# Mezzanine_9DOF.net
KiCad netlist of a schematic drawn in EAGLE
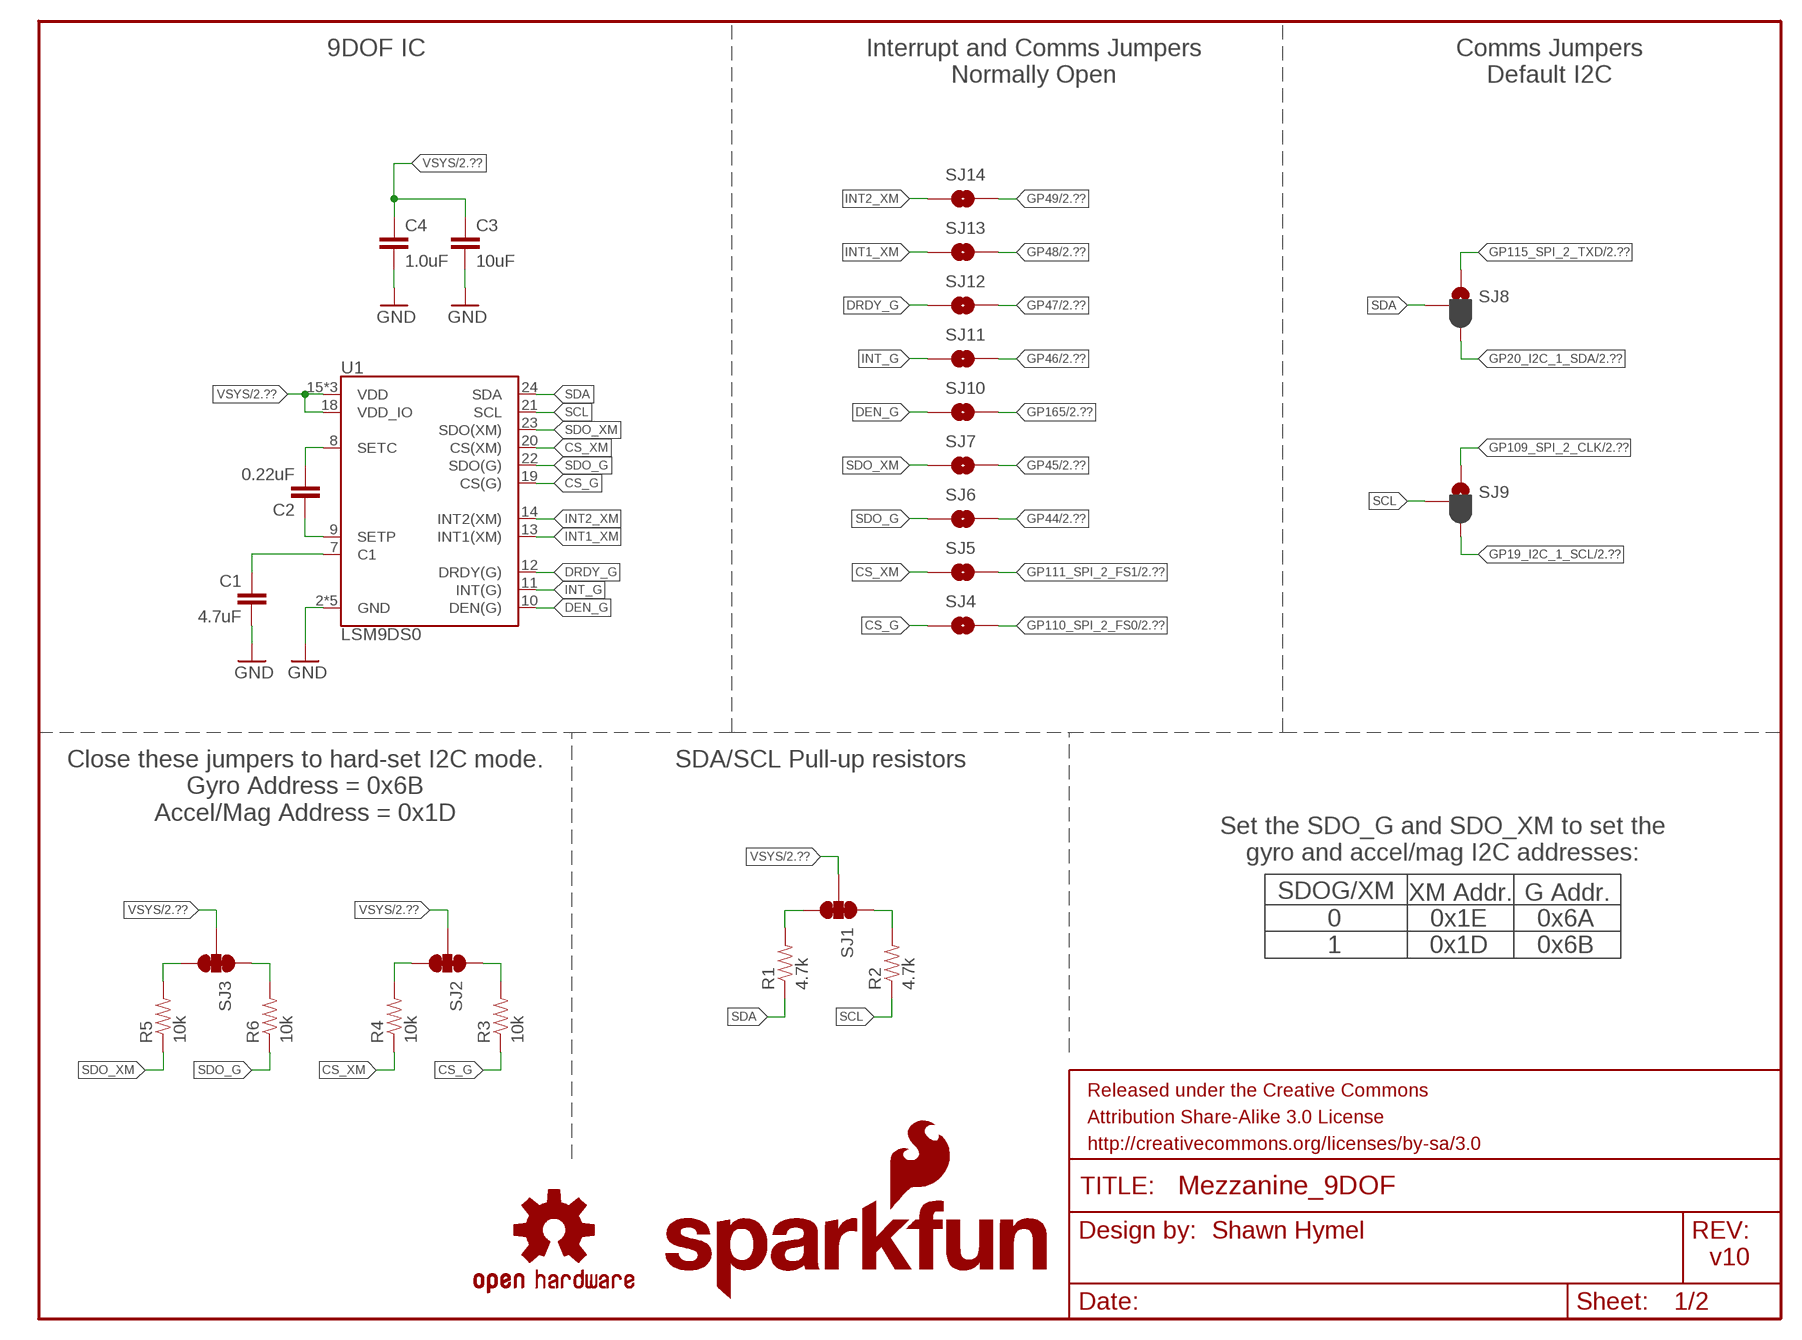
[diagram p0: schematic, sheet 1]
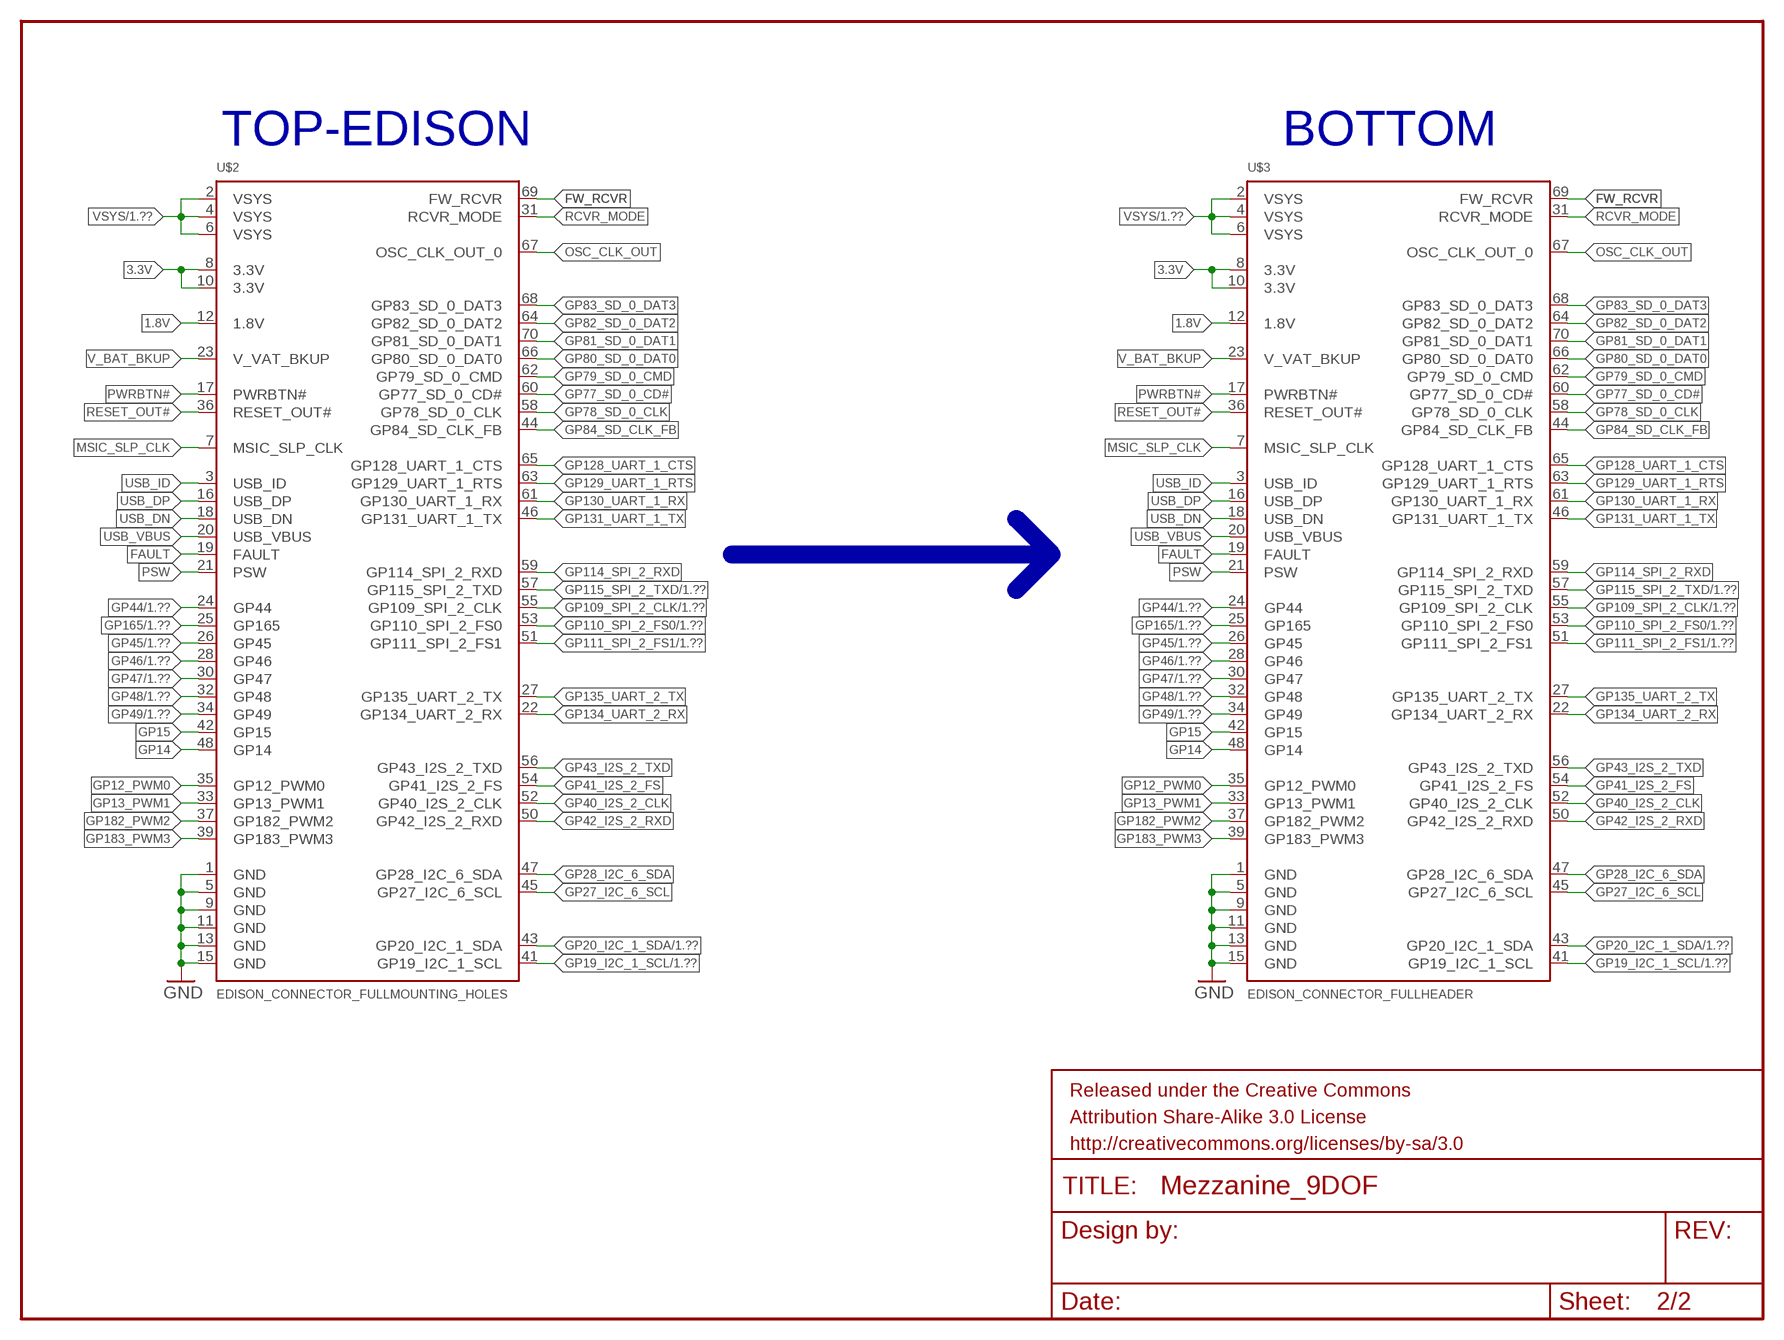
[diagram p1: schematic, sheet 2]

(export (version "E")
  (design (tool "Eeschema 10.0.6"))
  (components
    (comp (ref "FRAME2")
      (value "FRAME-LETTER")
      (footprint "eagle-import:CREATIVE_COMMONS")
      (libsource (lib "eagle-import") (part "FRAME-LETTER"))
    )
    (comp (ref "U$2")
      (value "EDISON_CONNECTOR_FULLMOUNTING_HOLES")
      (footprint "eagle-import:EDISON_DAUGHTER")
      (libsource (lib "eagle-import") (part "EDISON_CONNECTOR_FULLMOUNTING_HOLES"))
    )
    (comp (ref "U$3")
      (value "EDISON_CONNECTOR_FULLHEADER")
      (footprint "eagle-import:DF40C-70DP-0.4(51)")
      (libsource (lib "eagle-import") (part "EDISON_CONNECTOR_FULLHEADER"))
    )
    (comp (ref "C1")
      (value "4.7uF")
      (footprint "eagle-import:0603-CAP")
      (libsource (lib "eagle-import") (part "4.7UF-6.3V-10%(0603)0603"))
    )
    (comp (ref "C2")
      (value "0.22uF")
      (footprint "eagle-import:0603-CAP")
      (libsource (lib "eagle-import") (part "0.22UF-25V-10%(0603)"))
    )
    (comp (ref "C3")
      (value "10uF")
      (footprint "eagle-import:0805")
      (libsource (lib "eagle-import") (part "CAP0805"))
    )
    (comp (ref "C4")
      (value "1.0uF")
      (footprint "eagle-import:0603-CAP")
      (libsource (lib "eagle-import") (part "1.0UF-16V-10%(0603)"))
    )
    (comp (ref "FRAME1")
      (value "FRAME-LETTER")
      (footprint "eagle-import:CREATIVE_COMMONS")
      (libsource (lib "eagle-import") (part "FRAME-LETTER"))
    )
    (comp (ref "LOGO2")
      (value "OSHW-LOGOS")
      (footprint "eagle-import:OSHW-LOGO-S")
      (libsource (lib "eagle-import") (part "OSHW-LOGOS"))
    )
    (comp (ref "LOGO3")
      (value "SFE_LOGO_NAME_FLAME.1_INCH")
      (footprint "eagle-import:SFE_LOGO_NAME_FLAME_.1")
      (libsource (lib "eagle-import") (part "SFE_LOGO_NAME_FLAME.1_INCH"))
    )
    (comp (ref "R1")
      (value "4.7k")
      (footprint "eagle-import:0603-RES")
      (libsource (lib "eagle-import") (part "10K-1%RES-00824"))
    )
    (comp (ref "R2")
      (value "4.7k")
      (footprint "eagle-import:0603-RES")
      (libsource (lib "eagle-import") (part "10K-1%RES-00824"))
    )
    (comp (ref "R3")
      (value "10k")
      (footprint "eagle-import:0603-RES")
      (libsource (lib "eagle-import") (part "10K-1%RES-00824"))
    )
    (comp (ref "R4")
      (value "10k")
      (footprint "eagle-import:0603-RES")
      (libsource (lib "eagle-import") (part "10K-1%RES-00824"))
    )
    (comp (ref "R5")
      (value "10k")
      (footprint "eagle-import:0603-RES")
      (libsource (lib "eagle-import") (part "10K-1%RES-00824"))
    )
    (comp (ref "R6")
      (value "10k")
      (footprint "eagle-import:0603-RES")
      (libsource (lib "eagle-import") (part "10K-1%RES-00824"))
    )
    (comp (ref "SJ1")
      (value "SOLDERJUMPER_2WAYS")
      (footprint "eagle-import:SJ_3")
      (libsource (lib "eagle-import") (part "SOLDERJUMPER_2WAYS"))
    )
    (comp (ref "SJ2")
      (value "SOLDERJUMPER_2WAYS")
      (footprint "eagle-import:SJ_3")
      (libsource (lib "eagle-import") (part "SOLDERJUMPER_2WAYS"))
    )
    (comp (ref "SJ3")
      (value "SOLDERJUMPER_2WAYS")
      (footprint "eagle-import:SJ_3")
      (libsource (lib "eagle-import") (part "SOLDERJUMPER_2WAYS"))
    )
    (comp (ref "SJ4")
      (value "JUMPER-PAD-2-NOYES_SILK")
      (footprint "eagle-import:PAD-JUMPER-2-NO_YES_SILK")
      (libsource (lib "eagle-import") (part "JUMPER-PAD-2-NOYES_SILK"))
    )
    (comp (ref "SJ5")
      (value "JUMPER-PAD-2-NOYES_SILK")
      (footprint "eagle-import:PAD-JUMPER-2-NO_YES_SILK")
      (libsource (lib "eagle-import") (part "JUMPER-PAD-2-NOYES_SILK"))
    )
    (comp (ref "SJ6")
      (value "JUMPER-PAD-2-NOYES_SILK")
      (footprint "eagle-import:PAD-JUMPER-2-NO_YES_SILK")
      (libsource (lib "eagle-import") (part "JUMPER-PAD-2-NOYES_SILK"))
    )
    (comp (ref "SJ7")
      (value "JUMPER-PAD-2-NOYES_SILK")
      (footprint "eagle-import:PAD-JUMPER-2-NO_YES_SILK")
      (libsource (lib "eagle-import") (part "JUMPER-PAD-2-NOYES_SILK"))
    )
    (comp (ref "SJ8")
      (value "JUMPER-PAD-3-2OF3_NC_BY_PASTE")
      (footprint "eagle-import:PAD-JUMPER-3-2OF3_NC_BY_PASTE_YES_SILK_FULL_BOX")
      (libsource (lib "eagle-import") (part "JUMPER-PAD-3-2OF3_NC_BY_PASTE"))
    )
    (comp (ref "SJ9")
      (value "JUMPER-PAD-3-2OF3_NC_BY_PASTE")
      (footprint "eagle-import:PAD-JUMPER-3-2OF3_NC_BY_PASTE_YES_SILK_FULL_BOX")
      (libsource (lib "eagle-import") (part "JUMPER-PAD-3-2OF3_NC_BY_PASTE"))
    )
    (comp (ref "SJ10")
      (value "JUMPER-PAD-2-NOYES_SILK")
      (footprint "eagle-import:PAD-JUMPER-2-NO_YES_SILK")
      (libsource (lib "eagle-import") (part "JUMPER-PAD-2-NOYES_SILK"))
    )
    (comp (ref "SJ11")
      (value "JUMPER-PAD-2-NOYES_SILK")
      (footprint "eagle-import:PAD-JUMPER-2-NO_YES_SILK")
      (libsource (lib "eagle-import") (part "JUMPER-PAD-2-NOYES_SILK"))
    )
    (comp (ref "SJ12")
      (value "JUMPER-PAD-2-NOYES_SILK")
      (footprint "eagle-import:PAD-JUMPER-2-NO_YES_SILK")
      (libsource (lib "eagle-import") (part "JUMPER-PAD-2-NOYES_SILK"))
    )
    (comp (ref "SJ13")
      (value "JUMPER-PAD-2-NOYES_SILK")
      (footprint "eagle-import:PAD-JUMPER-2-NO_YES_SILK")
      (libsource (lib "eagle-import") (part "JUMPER-PAD-2-NOYES_SILK"))
    )
    (comp (ref "SJ14")
      (value "JUMPER-PAD-2-NOYES_SILK")
      (footprint "eagle-import:PAD-JUMPER-2-NO_YES_SILK")
      (libsource (lib "eagle-import") (part "JUMPER-PAD-2-NOYES_SILK"))
    )
    (comp (ref "U1")
      (value "LSM9DS0")
      (footprint "eagle-import:LGA-24")
      (libsource (lib "eagle-import") (part "LSM9DS0"))
    )
  )
  (nets
    (net (code "1") (name "1.8V") (class "Default")
      (node (ref "U$2") (pin "12") (pinfunction "1.8V_12") (pintype "bidirectional"))
      (node (ref "U$3") (pin "12") (pinfunction "1.8V_12") (pintype "bidirectional"))
    )
    (net (code "2") (name "3.3V") (class "Default")
      (node (ref "U$2") (pin "10") (pinfunction "3.3V_10") (pintype "bidirectional"))
      (node (ref "U$2") (pin "8") (pinfunction "3.3V_8") (pintype "bidirectional"))
      (node (ref "U$3") (pin "10") (pinfunction "3.3V_10") (pintype "bidirectional"))
      (node (ref "U$3") (pin "8") (pinfunction "3.3V_8") (pintype "bidirectional"))
    )
    (net (code "3") (name "CS_G") (class "Default")
      (node (ref "R3") (pin "1") (pinfunction "1_1") (pintype "passive"))
      (node (ref "SJ4") (pin "1") (pinfunction "1_1") (pintype "passive"))
      (node (ref "U1") (pin "19") (pinfunction "CS(G)_19") (pintype "bidirectional"))
    )
    (net (code "4") (name "CS_XM") (class "Default")
      (node (ref "R4") (pin "1") (pinfunction "1_1") (pintype "passive"))
      (node (ref "SJ5") (pin "1") (pinfunction "1_1") (pintype "passive"))
      (node (ref "U1") (pin "20") (pinfunction "CS(XM)_20") (pintype "bidirectional"))
    )
    (net (code "5") (name "DEN_G") (class "Default")
      (node (ref "SJ10") (pin "1") (pinfunction "1_1") (pintype "passive"))
      (node (ref "U1") (pin "10") (pinfunction "DEN(G)_10") (pintype "bidirectional"))
    )
    (net (code "6") (name "DRDY_G") (class "Default")
      (node (ref "SJ12") (pin "1") (pinfunction "1_1") (pintype "passive"))
      (node (ref "U1") (pin "12") (pinfunction "DRDY(G)_12") (pintype "bidirectional"))
    )
    (net (code "7") (name "FAULT") (class "Default")
      (node (ref "U$2") (pin "19") (pinfunction "FAULT_19") (pintype "bidirectional"))
      (node (ref "U$3") (pin "19") (pinfunction "FAULT_19") (pintype "bidirectional"))
    )
    (net (code "8") (name "FW_RCVR") (class "Default")
      (node (ref "U$2") (pin "69") (pinfunction "FW_RCVR_69") (pintype "bidirectional"))
      (node (ref "U$3") (pin "69") (pinfunction "FW_RCVR_69") (pintype "bidirectional"))
    )
    (net (code "9") (name "GND") (class "Default")
      (node (ref "C1") (pin "2") (pinfunction "2_2") (pintype "passive"))
      (node (ref "C3") (pin "2") (pinfunction "2_2") (pintype "passive"))
      (node (ref "C4") (pin "2") (pinfunction "2_2") (pintype "passive"))
      (node (ref "U$2") (pin "1") (pinfunction "GND_1") (pintype "bidirectional"))
      (node (ref "U$2") (pin "11") (pinfunction "GND_11") (pintype "bidirectional"))
      (node (ref "U$2") (pin "13") (pinfunction "GND_13") (pintype "bidirectional"))
      (node (ref "U$2") (pin "15") (pinfunction "GND_15") (pintype "bidirectional"))
      (node (ref "U$2") (pin "5") (pinfunction "GND_5") (pintype "bidirectional"))
      (node (ref "U$2") (pin "9") (pinfunction "GND_9") (pintype "bidirectional"))
      (node (ref "U$3") (pin "1") (pinfunction "GND_1") (pintype "bidirectional"))
      (node (ref "U$3") (pin "11") (pinfunction "GND_11") (pintype "bidirectional"))
      (node (ref "U$3") (pin "13") (pinfunction "GND_13") (pintype "bidirectional"))
      (node (ref "U$3") (pin "15") (pinfunction "GND_15") (pintype "bidirectional"))
      (node (ref "U$3") (pin "5") (pinfunction "GND_5") (pintype "bidirectional"))
      (node (ref "U$3") (pin "9") (pinfunction "GND_9") (pintype "bidirectional"))
      (node (ref "U1") (pin "2") (pinfunction "GND_2") (pintype "bidirectional"))
      (node (ref "U1") (pin "3") (pinfunction "GND_3") (pintype "bidirectional"))
      (node (ref "U1") (pin "4") (pinfunction "GND_4") (pintype "bidirectional"))
      (node (ref "U1") (pin "5") (pinfunction "GND_5") (pintype "bidirectional"))
      (node (ref "U1") (pin "6") (pinfunction "GND_6") (pintype "bidirectional"))
    )
    (net (code "10") (name "GP12_PWM0") (class "Default")
      (node (ref "U$2") (pin "35") (pinfunction "GP12_PWM0_35") (pintype "bidirectional"))
      (node (ref "U$3") (pin "35") (pinfunction "GP12_PWM0_35") (pintype "bidirectional"))
    )
    (net (code "11") (name "GP13_PWM1") (class "Default")
      (node (ref "U$2") (pin "33") (pinfunction "GP13_PWM1_33") (pintype "bidirectional"))
      (node (ref "U$3") (pin "33") (pinfunction "GP13_PWM1_33") (pintype "bidirectional"))
    )
    (net (code "12") (name "GP14") (class "Default")
      (node (ref "U$2") (pin "48") (pinfunction "GP14_48") (pintype "bidirectional"))
      (node (ref "U$3") (pin "48") (pinfunction "GP14_48") (pintype "bidirectional"))
    )
    (net (code "13") (name "GP15") (class "Default")
      (node (ref "U$2") (pin "42") (pinfunction "GP15_42") (pintype "bidirectional"))
      (node (ref "U$3") (pin "42") (pinfunction "GP15_42") (pintype "bidirectional"))
    )
    (net (code "14") (name "GP19_I2C_1_SCL") (class "Default")
      (node (ref "SJ9") (pin "3") (pinfunction "3_3") (pintype "passive"))
      (node (ref "U$2") (pin "41") (pinfunction "GP19_I2C_1_SCL_41") (pintype "bidirectional"))
      (node (ref "U$3") (pin "41") (pinfunction "GP19_I2C_1_SCL_41") (pintype "bidirectional"))
    )
    (net (code "15") (name "GP20_I2C_1_SDA") (class "Default")
      (node (ref "SJ8") (pin "3") (pinfunction "3_3") (pintype "passive"))
      (node (ref "U$2") (pin "43") (pinfunction "GP20_I2C_1_SDA_43") (pintype "bidirectional"))
      (node (ref "U$3") (pin "43") (pinfunction "GP20_I2C_1_SDA_43") (pintype "bidirectional"))
    )
    (net (code "16") (name "GP27_I2C_6_SCL") (class "Default")
      (node (ref "U$2") (pin "45") (pinfunction "GP27_I2C_6_SCL_45") (pintype "bidirectional"))
      (node (ref "U$3") (pin "45") (pinfunction "GP27_I2C_6_SCL_45") (pintype "bidirectional"))
    )
    (net (code "17") (name "GP28_I2C_6_SDA") (class "Default")
      (node (ref "U$2") (pin "47") (pinfunction "GP28_I2C_6_SDA_47") (pintype "bidirectional"))
      (node (ref "U$3") (pin "47") (pinfunction "GP28_I2C_6_SDA_47") (pintype "bidirectional"))
    )
    (net (code "18") (name "GP40_I2S_2_CLK") (class "Default")
      (node (ref "U$2") (pin "52") (pinfunction "GP40_I2S_2_CLK_52") (pintype "bidirectional"))
      (node (ref "U$3") (pin "52") (pinfunction "GP40_I2S_2_CLK_52") (pintype "bidirectional"))
    )
    (net (code "19") (name "GP41_I2S_2_FS") (class "Default")
      (node (ref "U$2") (pin "54") (pinfunction "GP41_I2S_2_FS_54") (pintype "bidirectional"))
      (node (ref "U$3") (pin "54") (pinfunction "GP41_I2S_2_FS_54") (pintype "bidirectional"))
    )
    (net (code "20") (name "GP42_I2S_2_RXD") (class "Default")
      (node (ref "U$2") (pin "50") (pinfunction "GP42_I2S_2_RXD_50") (pintype "bidirectional"))
      (node (ref "U$3") (pin "50") (pinfunction "GP42_I2S_2_RXD_50") (pintype "bidirectional"))
    )
    (net (code "21") (name "GP43_I2S_2_TXD") (class "Default")
      (node (ref "U$2") (pin "56") (pinfunction "GP43_I2S_2_TXD_56") (pintype "bidirectional"))
      (node (ref "U$3") (pin "56") (pinfunction "GP43_I2S_2_TXD_56") (pintype "bidirectional"))
    )
    (net (code "22") (name "GP44") (class "Default")
      (node (ref "SJ6") (pin "2") (pinfunction "2_2") (pintype "passive"))
      (node (ref "U$2") (pin "24") (pinfunction "GP44_24") (pintype "bidirectional"))
      (node (ref "U$3") (pin "24") (pinfunction "GP44_24") (pintype "bidirectional"))
    )
    (net (code "23") (name "GP45") (class "Default")
      (node (ref "SJ7") (pin "2") (pinfunction "2_2") (pintype "passive"))
      (node (ref "U$2") (pin "26") (pinfunction "GP45_26") (pintype "bidirectional"))
      (node (ref "U$3") (pin "26") (pinfunction "GP45_26") (pintype "bidirectional"))
    )
    (net (code "24") (name "GP46") (class "Default")
      (node (ref "SJ11") (pin "2") (pinfunction "2_2") (pintype "passive"))
      (node (ref "U$2") (pin "28") (pinfunction "GP46_28") (pintype "bidirectional"))
      (node (ref "U$3") (pin "28") (pinfunction "GP46_28") (pintype "bidirectional"))
    )
    (net (code "25") (name "GP47") (class "Default")
      (node (ref "SJ12") (pin "2") (pinfunction "2_2") (pintype "passive"))
      (node (ref "U$2") (pin "30") (pinfunction "GP47_30") (pintype "bidirectional"))
      (node (ref "U$3") (pin "30") (pinfunction "GP47_30") (pintype "bidirectional"))
    )
    (net (code "26") (name "GP48") (class "Default")
      (node (ref "SJ13") (pin "2") (pinfunction "2_2") (pintype "passive"))
      (node (ref "U$2") (pin "32") (pinfunction "GP48_32") (pintype "bidirectional"))
      (node (ref "U$3") (pin "32") (pinfunction "GP48_32") (pintype "bidirectional"))
    )
    (net (code "27") (name "GP49") (class "Default")
      (node (ref "SJ14") (pin "2") (pinfunction "2_2") (pintype "passive"))
      (node (ref "U$2") (pin "34") (pinfunction "GP49_34") (pintype "bidirectional"))
      (node (ref "U$3") (pin "34") (pinfunction "GP49_34") (pintype "bidirectional"))
    )
    (net (code "28") (name "GP77_SD_0_CD#") (class "Default")
      (node (ref "U$2") (pin "60") (pinfunction "GP77_SD_0_CD#_60") (pintype "bidirectional"))
      (node (ref "U$3") (pin "60") (pinfunction "GP77_SD_0_CD#_60") (pintype "bidirectional"))
    )
    (net (code "29") (name "GP78_SD_0_CLK") (class "Default")
      (node (ref "U$2") (pin "58") (pinfunction "GP78_SD_0_CLK_58") (pintype "bidirectional"))
      (node (ref "U$3") (pin "58") (pinfunction "GP78_SD_0_CLK_58") (pintype "bidirectional"))
    )
    (net (code "30") (name "GP79_SD_0_CMD") (class "Default")
      (node (ref "U$2") (pin "62") (pinfunction "GP79_SD_0_CMD_62") (pintype "bidirectional"))
      (node (ref "U$3") (pin "62") (pinfunction "GP79_SD_0_CMD_62") (pintype "bidirectional"))
    )
    (net (code "31") (name "GP80_SD_0_DAT0") (class "Default")
      (node (ref "U$2") (pin "66") (pinfunction "GP80_SD_0_DAT0_66") (pintype "bidirectional"))
      (node (ref "U$3") (pin "66") (pinfunction "GP80_SD_0_DAT0_66") (pintype "bidirectional"))
    )
    (net (code "32") (name "GP81_SD_0_DAT1") (class "Default")
      (node (ref "U$2") (pin "70") (pinfunction "GP81_SD_0_DAT1_70") (pintype "bidirectional"))
      (node (ref "U$3") (pin "70") (pinfunction "GP81_SD_0_DAT1_70") (pintype "bidirectional"))
    )
    (net (code "33") (name "GP82_SD_0_DAT2") (class "Default")
      (node (ref "U$2") (pin "64") (pinfunction "GP82_SD_0_DAT2_64") (pintype "bidirectional"))
      (node (ref "U$3") (pin "64") (pinfunction "GP82_SD_0_DAT2_64") (pintype "bidirectional"))
    )
    (net (code "34") (name "GP83_SD_0_DAT3") (class "Default")
      (node (ref "U$2") (pin "68") (pinfunction "GP83_SD_0_DAT3_68") (pintype "bidirectional"))
      (node (ref "U$3") (pin "68") (pinfunction "GP83_SD_0_DAT3_68") (pintype "bidirectional"))
    )
    (net (code "35") (name "GP84_SD_CLK_FB") (class "Default")
      (node (ref "U$2") (pin "44") (pinfunction "GP84_SD_CLK_FB_44") (pintype "bidirectional"))
      (node (ref "U$3") (pin "44") (pinfunction "GP84_SD_CLK_FB_44") (pintype "bidirectional"))
    )
    (net (code "36") (name "GP109_SPI_2_CLK") (class "Default")
      (node (ref "SJ9") (pin "1") (pinfunction "1_1") (pintype "passive"))
      (node (ref "U$2") (pin "55") (pinfunction "GP109_SPI_2_CLK_55") (pintype "bidirectional"))
      (node (ref "U$3") (pin "55") (pinfunction "GP109_SPI_2_CLK_55") (pintype "bidirectional"))
    )
    (net (code "37") (name "GP110_SPI_2_FS0") (class "Default")
      (node (ref "SJ4") (pin "2") (pinfunction "2_2") (pintype "passive"))
      (node (ref "U$2") (pin "53") (pinfunction "GP110_SPI_2_FS0_53") (pintype "bidirectional"))
      (node (ref "U$3") (pin "53") (pinfunction "GP110_SPI_2_FS0_53") (pintype "bidirectional"))
    )
    (net (code "38") (name "GP111_SPI_2_FS1") (class "Default")
      (node (ref "SJ5") (pin "2") (pinfunction "2_2") (pintype "passive"))
      (node (ref "U$2") (pin "51") (pinfunction "GP111_SPI_2_FS1_51") (pintype "bidirectional"))
      (node (ref "U$3") (pin "51") (pinfunction "GP111_SPI_2_FS1_51") (pintype "bidirectional"))
    )
    (net (code "39") (name "GP114_SPI_2_RXD") (class "Default")
      (node (ref "U$2") (pin "59") (pinfunction "GP114_SPI_2_RXD_59") (pintype "bidirectional"))
      (node (ref "U$3") (pin "59") (pinfunction "GP114_SPI_2_RXD_59") (pintype "bidirectional"))
    )
    (net (code "40") (name "GP115_SPI_2_TXD") (class "Default")
      (node (ref "SJ8") (pin "1") (pinfunction "1_1") (pintype "passive"))
      (node (ref "U$2") (pin "57") (pinfunction "GP115_SPI_2_TXD_57") (pintype "bidirectional"))
      (node (ref "U$3") (pin "57") (pinfunction "GP115_SPI_2_TXD_57") (pintype "bidirectional"))
    )
    (net (code "41") (name "GP128_UART_1_CTS") (class "Default")
      (node (ref "U$2") (pin "65") (pinfunction "GP128_UART_1_CTS_65") (pintype "bidirectional"))
      (node (ref "U$3") (pin "65") (pinfunction "GP128_UART_1_CTS_65") (pintype "bidirectional"))
    )
    (net (code "42") (name "GP129_UART_1_RTS") (class "Default")
      (node (ref "U$2") (pin "63") (pinfunction "GP129_UART_1_RTS_63") (pintype "bidirectional"))
      (node (ref "U$3") (pin "63") (pinfunction "GP129_UART_1_RTS_63") (pintype "bidirectional"))
    )
    (net (code "43") (name "GP130_UART_1_RX") (class "Default")
      (node (ref "U$2") (pin "61") (pinfunction "GP130_UART_1_RX_61") (pintype "bidirectional"))
      (node (ref "U$3") (pin "61") (pinfunction "GP130_UART_1_RX_61") (pintype "bidirectional"))
    )
    (net (code "44") (name "GP131_UART_1_TX") (class "Default")
      (node (ref "U$2") (pin "46") (pinfunction "GP131_UART_1_TX_46") (pintype "bidirectional"))
      (node (ref "U$3") (pin "46") (pinfunction "GP131_UART_1_TX_46") (pintype "bidirectional"))
    )
    (net (code "45") (name "GP134_UART_2_RX") (class "Default")
      (node (ref "U$2") (pin "22") (pinfunction "GP134_UART_2_RX_22") (pintype "bidirectional"))
      (node (ref "U$3") (pin "22") (pinfunction "GP134_UART_2_RX_22") (pintype "bidirectional"))
    )
    (net (code "46") (name "GP135_UART_2_TX") (class "Default")
      (node (ref "U$2") (pin "27") (pinfunction "GP135_UART_2_TX_27") (pintype "bidirectional"))
      (node (ref "U$3") (pin "27") (pinfunction "GP135_UART_2_TX_27") (pintype "bidirectional"))
    )
    (net (code "47") (name "GP165") (class "Default")
      (node (ref "SJ10") (pin "2") (pinfunction "2_2") (pintype "passive"))
      (node (ref "U$2") (pin "25") (pinfunction "GP165_25") (pintype "bidirectional"))
      (node (ref "U$3") (pin "25") (pinfunction "GP165_25") (pintype "bidirectional"))
    )
    (net (code "48") (name "GP182_PWM2") (class "Default")
      (node (ref "U$2") (pin "37") (pinfunction "GP182_PWM2_37") (pintype "bidirectional"))
      (node (ref "U$3") (pin "37") (pinfunction "GP182_PWM2_37") (pintype "bidirectional"))
    )
    (net (code "49") (name "GP183_PWM3") (class "Default")
      (node (ref "U$2") (pin "39") (pinfunction "GP183_PWM3_39") (pintype "bidirectional"))
      (node (ref "U$3") (pin "39") (pinfunction "GP183_PWM3_39") (pintype "bidirectional"))
    )
    (net (code "50") (name "INT1_XM") (class "Default")
      (node (ref "SJ13") (pin "1") (pinfunction "1_1") (pintype "passive"))
      (node (ref "U1") (pin "13") (pinfunction "INT1(XM)_13") (pintype "bidirectional"))
    )
    (net (code "51") (name "INT2_XM") (class "Default")
      (node (ref "SJ14") (pin "1") (pinfunction "1_1") (pintype "passive"))
      (node (ref "U1") (pin "14") (pinfunction "INT2(XM)_14") (pintype "bidirectional"))
    )
    (net (code "52") (name "INT_G") (class "Default")
      (node (ref "SJ11") (pin "1") (pinfunction "1_1") (pintype "passive"))
      (node (ref "U1") (pin "11") (pinfunction "INT(G)_11") (pintype "bidirectional"))
    )
    (net (code "53") (name "MSIC_SLP_CLK") (class "Default")
      (node (ref "U$2") (pin "7") (pinfunction "MSIC_SLP_CLK_7") (pintype "bidirectional"))
      (node (ref "U$3") (pin "7") (pinfunction "MSIC_SLP_CLK_7") (pintype "bidirectional"))
    )
    (net (code "54") (name "Net-(R1-Pad2)") (class "Default")
      (node (ref "R1") (pin "2") (pinfunction "2_2") (pintype "passive"))
      (node (ref "SJ1") (pin "3") (pinfunction "3_3") (pintype "passive"))
    )
    (net (code "55") (name "Net-(R2-Pad2)") (class "Default")
      (node (ref "R2") (pin "2") (pinfunction "2_2") (pintype "passive"))
      (node (ref "SJ1") (pin "1") (pinfunction "1_1") (pintype "passive"))
    )
    (net (code "56") (name "Net-(R3-Pad2)") (class "Default")
      (node (ref "R3") (pin "2") (pinfunction "2_2") (pintype "passive"))
      (node (ref "SJ2") (pin "1") (pinfunction "1_1") (pintype "passive"))
    )
    (net (code "57") (name "Net-(R4-Pad2)") (class "Default")
      (node (ref "R4") (pin "2") (pinfunction "2_2") (pintype "passive"))
      (node (ref "SJ2") (pin "3") (pinfunction "3_3") (pintype "passive"))
    )
    (net (code "58") (name "Net-(R5-Pad2)") (class "Default")
      (node (ref "R5") (pin "2") (pinfunction "2_2") (pintype "passive"))
      (node (ref "SJ3") (pin "3") (pinfunction "3_3") (pintype "passive"))
    )
    (net (code "59") (name "Net-(R6-Pad2)") (class "Default")
      (node (ref "R6") (pin "2") (pinfunction "2_2") (pintype "passive"))
      (node (ref "SJ3") (pin "1") (pinfunction "1_1") (pintype "passive"))
    )
    (net (code "60") (name "Net-(U1-C1)") (class "Default")
      (node (ref "C1") (pin "1") (pinfunction "1_1") (pintype "passive"))
      (node (ref "U1") (pin "7") (pinfunction "C1_7") (pintype "bidirectional"))
    )
    (net (code "61") (name "Net-(U1-SETC)") (class "Default")
      (node (ref "C2") (pin "2") (pinfunction "2_2") (pintype "passive"))
      (node (ref "U1") (pin "8") (pinfunction "SETC_8") (pintype "bidirectional"))
    )
    (net (code "62") (name "Net-(U1-SETP)") (class "Default")
      (node (ref "C2") (pin "1") (pinfunction "1_1") (pintype "passive"))
      (node (ref "U1") (pin "9") (pinfunction "SETP_9") (pintype "bidirectional"))
    )
    (net (code "63") (name "OSC_CLK_OUT") (class "Default")
      (node (ref "U$2") (pin "67") (pinfunction "OSC_CLK_OUT_0_67") (pintype "bidirectional"))
      (node (ref "U$3") (pin "67") (pinfunction "OSC_CLK_OUT_0_67") (pintype "bidirectional"))
    )
    (net (code "64") (name "PSW") (class "Default")
      (node (ref "U$2") (pin "21") (pinfunction "PSW_21") (pintype "bidirectional"))
      (node (ref "U$3") (pin "21") (pinfunction "PSW_21") (pintype "bidirectional"))
    )
    (net (code "65") (name "PWRBTN#") (class "Default")
      (node (ref "U$2") (pin "17") (pinfunction "PWRBTN#_17") (pintype "bidirectional"))
      (node (ref "U$3") (pin "17") (pinfunction "PWRBTN#_17") (pintype "bidirectional"))
    )
    (net (code "66") (name "RCVR_MODE") (class "Default")
      (node (ref "U$2") (pin "31") (pinfunction "RCVR_MODE_31") (pintype "bidirectional"))
      (node (ref "U$3") (pin "31") (pinfunction "RCVR_MODE_31") (pintype "bidirectional"))
    )
    (net (code "67") (name "RESET_OUT#") (class "Default")
      (node (ref "U$2") (pin "36") (pinfunction "RESET_OUT#_36") (pintype "bidirectional"))
      (node (ref "U$3") (pin "36") (pinfunction "RESET_OUT#_36") (pintype "bidirectional"))
    )
    (net (code "68") (name "SCL") (class "Default")
      (node (ref "R2") (pin "1") (pinfunction "1_1") (pintype "passive"))
      (node (ref "SJ9") (pin "2") (pinfunction "2_2") (pintype "passive"))
      (node (ref "U1") (pin "21") (pinfunction "SCL_21") (pintype "bidirectional"))
    )
    (net (code "69") (name "SDA") (class "Default")
      (node (ref "R1") (pin "1") (pinfunction "1_1") (pintype "passive"))
      (node (ref "SJ8") (pin "2") (pinfunction "2_2") (pintype "passive"))
      (node (ref "U1") (pin "24") (pinfunction "SDA_24") (pintype "bidirectional"))
    )
    (net (code "70") (name "SDO_G") (class "Default")
      (node (ref "R6") (pin "1") (pinfunction "1_1") (pintype "passive"))
      (node (ref "SJ6") (pin "1") (pinfunction "1_1") (pintype "passive"))
      (node (ref "U1") (pin "22") (pinfunction "SDO(G)_22") (pintype "bidirectional"))
    )
    (net (code "71") (name "SDO_XM") (class "Default")
      (node (ref "R5") (pin "1") (pinfunction "1_1") (pintype "passive"))
      (node (ref "SJ7") (pin "1") (pinfunction "1_1") (pintype "passive"))
      (node (ref "U1") (pin "23") (pinfunction "SDO(XM)_23") (pintype "bidirectional"))
    )
    (net (code "72") (name "USB_DN") (class "Default")
      (node (ref "U$2") (pin "18") (pinfunction "USB_DN_18") (pintype "bidirectional"))
      (node (ref "U$3") (pin "18") (pinfunction "USB_DN_18") (pintype "bidirectional"))
    )
    (net (code "73") (name "USB_DP") (class "Default")
      (node (ref "U$2") (pin "16") (pinfunction "USB_DP_16") (pintype "bidirectional"))
      (node (ref "U$3") (pin "16") (pinfunction "USB_DP_16") (pintype "bidirectional"))
    )
    (net (code "74") (name "USB_ID") (class "Default")
      (node (ref "U$2") (pin "3") (pinfunction "USB_ID_3") (pintype "bidirectional"))
      (node (ref "U$3") (pin "3") (pinfunction "USB_ID_3") (pintype "bidirectional"))
    )
    (net (code "75") (name "USB_VBUS") (class "Default")
      (node (ref "U$2") (pin "20") (pinfunction "USB_VBUS_20") (pintype "bidirectional"))
      (node (ref "U$3") (pin "20") (pinfunction "USB_VBUS_20") (pintype "bidirectional"))
    )
    (net (code "76") (name "VSYS") (class "Default")
      (node (ref "C3") (pin "1") (pinfunction "1_1") (pintype "passive"))
      (node (ref "C4") (pin "1") (pinfunction "1_1") (pintype "passive"))
      (node (ref "SJ1") (pin "2") (pinfunction "2_2") (pintype "passive"))
      (node (ref "SJ2") (pin "2") (pinfunction "2_2") (pintype "passive"))
      (node (ref "SJ3") (pin "2") (pinfunction "2_2") (pintype "passive"))
      (node (ref "U$2") (pin "2") (pinfunction "VSYS_2") (pintype "bidirectional"))
      (node (ref "U$2") (pin "4") (pinfunction "VSYS_4") (pintype "bidirectional"))
      (node (ref "U$2") (pin "6") (pinfunction "VSYS_6") (pintype "bidirectional"))
      (node (ref "U$3") (pin "2") (pinfunction "VSYS_2") (pintype "bidirectional"))
      (node (ref "U$3") (pin "4") (pinfunction "VSYS_4") (pintype "bidirectional"))
      (node (ref "U$3") (pin "6") (pinfunction "VSYS_6") (pintype "bidirectional"))
      (node (ref "U1") (pin "15") (pinfunction "VDD_15") (pintype "bidirectional"))
      (node (ref "U1") (pin "16") (pinfunction "VDD_16") (pintype "bidirectional"))
      (node (ref "U1") (pin "17") (pinfunction "VDD_17") (pintype "bidirectional"))
      (node (ref "U1") (pin "18") (pinfunction "VDD_IO_18") (pintype "bidirectional"))
    )
    (net (code "77") (name "V_BAT_BKUP") (class "Default")
      (node (ref "U$2") (pin "23") (pinfunction "V_VAT_BKUP_23") (pintype "bidirectional"))
      (node (ref "U$3") (pin "23") (pinfunction "V_VAT_BKUP_23") (pintype "bidirectional"))
    )
  )
)
